# LED.net
KiCad netlist of a schematic drawn in Altium Designer
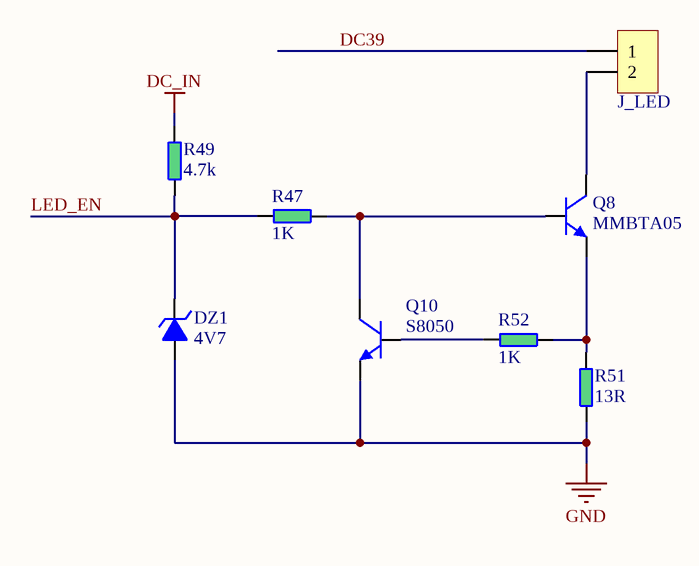
[diagram p0: LED.SchDoc]

(export (version "E")
  (design (tool "Eeschema 10.0.6"))
  (components
    (comp (ref "DZ1")
      (value "4V7")
      (footprint "D ZMM4V7-LL34")
      (description "稳压管")
      (libsource (lib "电子元件") (part "13.Diode - Zen"))
    )
    (comp (ref "J_LED") (value "Pin02") (footprint "XH2.54 2P") (libsource (lib "接插件") (part "Pin02")))
    (comp (ref "Q8")
      (value "MMBTA05")
      (footprint "BJT-MMBTA05/60V/0.5A-SOT23")
      (description "三极管 NPN")
      (libsource (lib "电子元件") (part "07.BJT(N)"))
    )
    (comp (ref "Q10")
      (value "S8050")
      (footprint "BJT-S8050-SOT23")
      (description "三极管 NPN")
      (libsource (lib "电子元件") (part "07.BJT(N)"))
    )
    (comp (ref "R47")
      (value "1K")
      (footprint "R 0805")
      (description "电阻")
      (libsource (lib "") (part "01.Res_1"))
    )
    (comp (ref "R49")
      (value "4.7k")
      (footprint "R 0603")
      (description "电阻")
      (libsource (lib "电子元件") (part "01.Res"))
    )
    (comp (ref "R51")
      (value "13R")
      (footprint "R 0805")
      (description "电阻")
      (libsource (lib "电子元件") (part "01.Res"))
    )
    (comp (ref "R52")
      (value "1K")
      (footprint "R 0603")
      (description "电阻")
      (libsource (lib "") (part "01.Res_1"))
    )
  )
  (nets
    (net (code "1") (name "/DC39") (class "Default")
      (node (ref "J_LED") (pin "1") (pinfunction "1_1") (pintype "passive"))
    )
    (net (code "2") (name "/LED_EN") (class "Default")
      (node (ref "DZ1") (pin "K") (pinfunction "K_K") (pintype "passive"))
      (node (ref "R47") (pin "1") (pinfunction "1_1") (pintype "passive"))
      (node (ref "R49") (pin "1") (pinfunction "1_1") (pintype "passive"))
    )
    (net (code "3") (name "DC_IN") (class "Default")
      (node (ref "R49") (pin "2") (pinfunction "2_2") (pintype "passive"))
    )
    (net (code "4") (name "GND") (class "Default")
      (node (ref "DZ1") (pin "A") (pinfunction "A_A") (pintype "passive"))
      (node (ref "Q10") (pin "E") (pinfunction "E_E") (pintype "passive"))
      (node (ref "R51") (pin "1") (pinfunction "1_1") (pintype "passive"))
    )
    (net (code "5") (name "Net-(J_LED-Pad2)") (class "Default")
      (node (ref "J_LED") (pin "2") (pinfunction "2_2") (pintype "passive"))
      (node (ref "Q8") (pin "C") (pinfunction "C_C") (pintype "passive"))
    )
    (net (code "6") (name "Net-(Q8-PadE)") (class "Default")
      (node (ref "Q8") (pin "E") (pinfunction "E_E") (pintype "passive"))
      (node (ref "R51") (pin "2") (pinfunction "2_2") (pintype "passive"))
      (node (ref "R52") (pin "2") (pinfunction "2_2") (pintype "passive"))
    )
    (net (code "7") (name "Net-(Q10-PadB)") (class "Default")
      (node (ref "Q10") (pin "B") (pinfunction "B_B") (pintype "passive"))
      (node (ref "R52") (pin "1") (pinfunction "1_1") (pintype "passive"))
    )
    (net (code "8") (name "Net-(Q10-PadC)") (class "Default")
      (node (ref "Q10") (pin "C") (pinfunction "C_C") (pintype "passive"))
      (node (ref "Q8") (pin "B") (pinfunction "B_B") (pintype "passive"))
      (node (ref "R47") (pin "2") (pinfunction "2_2") (pintype "passive"))
    )
  )
)
